# NTC.net
KiCad netlist of a schematic drawn in Altium Designer
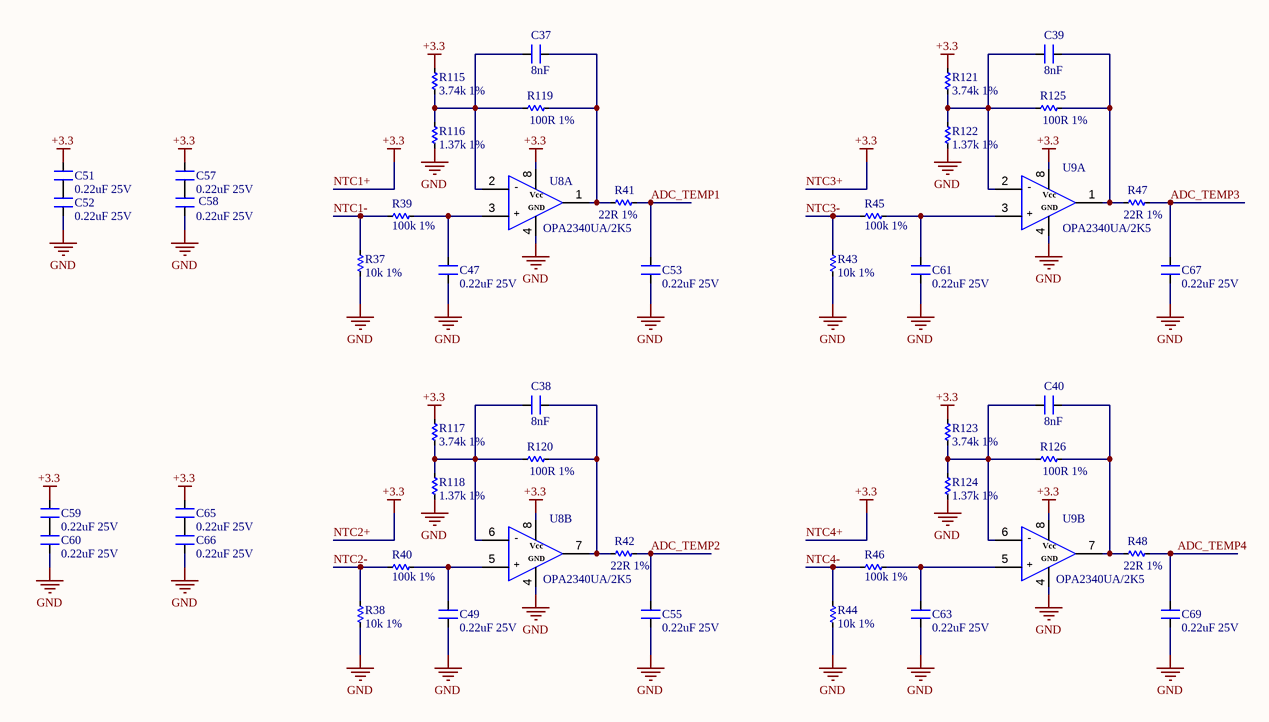
[diagram p0: NTC.SchDoc]

(export (version "E")
  (design (tool "Eeschema 10.0.6"))
  (components
    (comp (ref "C37")
      (value "8nF")
      (footprint "CN-SMD-0603")
      (libsource (lib "Sang_library") (part "Capacitors"))
    )
    (comp (ref "C38")
      (value "8nF")
      (footprint "CN-SMD-0603")
      (libsource (lib "Sang_library") (part "Capacitors"))
    )
    (comp (ref "C39")
      (value "8nF")
      (footprint "CN-SMD-0603")
      (libsource (lib "Sang_library") (part "Capacitors"))
    )
    (comp (ref "C40")
      (value "8nF")
      (footprint "CN-SMD-0603")
      (libsource (lib "Sang_library") (part "Capacitors"))
    )
    (comp (ref "C47")
      (value "0.22uF 25V")
      (footprint "CN-SMD-0603")
      (libsource (lib "Sang_library") (part "Capacitors"))
    )
    (comp (ref "C49")
      (value "0.22uF 25V")
      (footprint "CN-SMD-0603")
      (libsource (lib "Sang_library") (part "Capacitors"))
    )
    (comp (ref "C51")
      (value "0.22uF 25V")
      (footprint "CN-SMD-0603")
      (libsource (lib "Sang_library") (part "Capacitors"))
    )
    (comp (ref "C52")
      (value "0.22uF 25V")
      (footprint "CN-SMD-0603")
      (libsource (lib "Sang_library") (part "Capacitors"))
    )
    (comp (ref "C53")
      (value "0.22uF 25V")
      (footprint "CN-SMD-0603")
      (libsource (lib "Sang_library") (part "Capacitors"))
    )
    (comp (ref "C55")
      (value "0.22uF 25V")
      (footprint "CN-SMD-0603")
      (libsource (lib "Sang_library") (part "Capacitors"))
    )
    (comp (ref "C57")
      (value "0.22uF 25V")
      (footprint "CN-SMD-0603")
      (libsource (lib "Sang_library") (part "Capacitors"))
    )
    (comp (ref "C58")
      (value "0.22uF 25V")
      (footprint "CN-SMD-0603")
      (libsource (lib "Sang_library") (part "Capacitors"))
    )
    (comp (ref "C59")
      (value "0.22uF 25V")
      (footprint "CN-SMD-0603")
      (libsource (lib "Sang_library") (part "Capacitors"))
    )
    (comp (ref "C60")
      (value "0.22uF 25V")
      (footprint "CN-SMD-0603")
      (libsource (lib "Sang_library") (part "Capacitors"))
    )
    (comp (ref "C61")
      (value "0.22uF 25V")
      (footprint "CN-SMD-0603")
      (libsource (lib "Sang_library") (part "Capacitors"))
    )
    (comp (ref "C63")
      (value "0.22uF 25V")
      (footprint "CN-SMD-0603")
      (libsource (lib "Sang_library") (part "Capacitors"))
    )
    (comp (ref "C65")
      (value "0.22uF 25V")
      (footprint "CN-SMD-0603")
      (libsource (lib "Sang_library") (part "Capacitors"))
    )
    (comp (ref "C66")
      (value "0.22uF 25V")
      (footprint "CN-SMD-0603")
      (libsource (lib "Sang_library") (part "Capacitors"))
    )
    (comp (ref "C67")
      (value "0.22uF 25V")
      (footprint "CN-SMD-0603")
      (libsource (lib "Sang_library") (part "Capacitors"))
    )
    (comp (ref "C69")
      (value "0.22uF 25V")
      (footprint "CN-SMD-0603")
      (libsource (lib "Sang_library") (part "Capacitors"))
    )
    (comp (ref "R37")
      (value "10k 1%")
      (footprint "RES-SMD-0603")
      (description "SMD")
      (fields
        (field (name "MANUFACTURER") "Generic Components")
        (field (name "PUBLISHER") "Altium Hobart Technology Centre")
      )
      (libsource (lib "Sang_library") (part "Res SMD"))
    )
    (comp (ref "R38")
      (value "10k 1%")
      (footprint "RES-SMD-0603")
      (description "SMD")
      (fields
        (field (name "MANUFACTURER") "Generic Components")
        (field (name "PUBLISHER") "Altium Hobart Technology Centre")
      )
      (libsource (lib "Sang_library") (part "Res SMD"))
    )
    (comp (ref "R39")
      (value "100k 1%")
      (footprint "RES-SMD-0603")
      (description "SMD")
      (fields
        (field (name "MANUFACTURER") "Generic Components")
        (field (name "PUBLISHER") "Altium Hobart Technology Centre")
      )
      (libsource (lib "Sang_library") (part "Res SMD"))
    )
    (comp (ref "R40")
      (value "100k 1%")
      (footprint "RES-SMD-0603")
      (description "SMD")
      (fields
        (field (name "MANUFACTURER") "Generic Components")
        (field (name "PUBLISHER") "Altium Hobart Technology Centre")
      )
      (libsource (lib "Sang_library") (part "Res SMD"))
    )
    (comp (ref "R41")
      (value "22R 1%")
      (footprint "RES-SMD-0603")
      (description "SMD")
      (fields
        (field (name "MANUFACTURER") "Generic Components")
        (field (name "PUBLISHER") "Altium Hobart Technology Centre")
      )
      (libsource (lib "Sang_library") (part "Res SMD"))
    )
    (comp (ref "R42")
      (value "22R 1%")
      (footprint "RES-SMD-0603")
      (description "SMD")
      (fields
        (field (name "MANUFACTURER") "Generic Components")
        (field (name "PUBLISHER") "Altium Hobart Technology Centre")
      )
      (libsource (lib "Sang_library") (part "Res SMD"))
    )
    (comp (ref "R43")
      (value "10k 1%")
      (footprint "RES-SMD-0603")
      (description "SMD")
      (fields
        (field (name "MANUFACTURER") "Generic Components")
        (field (name "PUBLISHER") "Altium Hobart Technology Centre")
      )
      (libsource (lib "Sang_library") (part "Res SMD"))
    )
    (comp (ref "R44")
      (value "10k 1%")
      (footprint "RES-SMD-0603")
      (description "SMD")
      (fields
        (field (name "MANUFACTURER") "Generic Components")
        (field (name "PUBLISHER") "Altium Hobart Technology Centre")
      )
      (libsource (lib "Sang_library") (part "Res SMD"))
    )
    (comp (ref "R45")
      (value "100k 1%")
      (footprint "RES-SMD-0603")
      (description "SMD")
      (fields
        (field (name "MANUFACTURER") "Generic Components")
        (field (name "PUBLISHER") "Altium Hobart Technology Centre")
      )
      (libsource (lib "Sang_library") (part "Res SMD"))
    )
    (comp (ref "R46")
      (value "100k 1%")
      (footprint "RES-SMD-0603")
      (description "SMD")
      (fields
        (field (name "MANUFACTURER") "Generic Components")
        (field (name "PUBLISHER") "Altium Hobart Technology Centre")
      )
      (libsource (lib "Sang_library") (part "Res SMD"))
    )
    (comp (ref "R47")
      (value "22R 1%")
      (footprint "RES-SMD-0603")
      (description "SMD")
      (fields
        (field (name "MANUFACTURER") "Generic Components")
        (field (name "PUBLISHER") "Altium Hobart Technology Centre")
      )
      (libsource (lib "Sang_library") (part "Res SMD"))
    )
    (comp (ref "R48")
      (value "22R 1%")
      (footprint "RES-SMD-0603")
      (description "SMD")
      (fields
        (field (name "MANUFACTURER") "Generic Components")
        (field (name "PUBLISHER") "Altium Hobart Technology Centre")
      )
      (libsource (lib "Sang_library") (part "Res SMD"))
    )
    (comp (ref "R115")
      (value "3.74k 1%")
      (footprint "RES-SMD-0603")
      (description "SMD")
      (fields
        (field (name "MANUFACTURER") "Generic Components")
        (field (name "PUBLISHER") "Altium Hobart Technology Centre")
      )
      (libsource (lib "Sang_library") (part "Res SMD"))
    )
    (comp (ref "R116")
      (value "1.37k 1%")
      (footprint "RES-SMD-0603")
      (description "SMD")
      (fields
        (field (name "MANUFACTURER") "Generic Components")
        (field (name "PUBLISHER") "Altium Hobart Technology Centre")
      )
      (libsource (lib "Sang_library") (part "Res SMD"))
    )
    (comp (ref "R117")
      (value "3.74k 1%")
      (footprint "RES-SMD-0603")
      (description "SMD")
      (fields
        (field (name "MANUFACTURER") "Generic Components")
        (field (name "PUBLISHER") "Altium Hobart Technology Centre")
      )
      (libsource (lib "Sang_library") (part "Res SMD"))
    )
    (comp (ref "R118")
      (value "1.37k 1%")
      (footprint "RES-SMD-0603")
      (description "SMD")
      (fields
        (field (name "MANUFACTURER") "Generic Components")
        (field (name "PUBLISHER") "Altium Hobart Technology Centre")
      )
      (libsource (lib "Sang_library") (part "Res SMD"))
    )
    (comp (ref "R119")
      (value "100R 1%")
      (footprint "RES-SMD-0603")
      (description "SMD")
      (fields
        (field (name "MANUFACTURER") "Generic Components")
        (field (name "PUBLISHER") "Altium Hobart Technology Centre")
      )
      (libsource (lib "Sang_library") (part "Res SMD"))
    )
    (comp (ref "R120")
      (value "100R 1%")
      (footprint "RES-SMD-0603")
      (description "SMD")
      (fields
        (field (name "MANUFACTURER") "Generic Components")
        (field (name "PUBLISHER") "Altium Hobart Technology Centre")
      )
      (libsource (lib "Sang_library") (part "Res SMD"))
    )
    (comp (ref "R121")
      (value "3.74k 1%")
      (footprint "RES-SMD-0603")
      (description "SMD")
      (fields
        (field (name "MANUFACTURER") "Generic Components")
        (field (name "PUBLISHER") "Altium Hobart Technology Centre")
      )
      (libsource (lib "Sang_library") (part "Res SMD"))
    )
    (comp (ref "R122")
      (value "1.37k 1%")
      (footprint "RES-SMD-0603")
      (description "SMD")
      (fields
        (field (name "MANUFACTURER") "Generic Components")
        (field (name "PUBLISHER") "Altium Hobart Technology Centre")
      )
      (libsource (lib "Sang_library") (part "Res SMD"))
    )
    (comp (ref "R123")
      (value "3.74k 1%")
      (footprint "RES-SMD-0603")
      (description "SMD")
      (fields
        (field (name "MANUFACTURER") "Generic Components")
        (field (name "PUBLISHER") "Altium Hobart Technology Centre")
      )
      (libsource (lib "Sang_library") (part "Res SMD"))
    )
    (comp (ref "R124")
      (value "1.37k 1%")
      (footprint "RES-SMD-0603")
      (description "SMD")
      (fields
        (field (name "MANUFACTURER") "Generic Components")
        (field (name "PUBLISHER") "Altium Hobart Technology Centre")
      )
      (libsource (lib "Sang_library") (part "Res SMD"))
    )
    (comp (ref "R125")
      (value "100R 1%")
      (footprint "RES-SMD-0603")
      (description "SMD")
      (fields
        (field (name "MANUFACTURER") "Generic Components")
        (field (name "PUBLISHER") "Altium Hobart Technology Centre")
      )
      (libsource (lib "Sang_library") (part "Res SMD"))
    )
    (comp (ref "R126")
      (value "100R 1%")
      (footprint "RES-SMD-0603")
      (description "SMD")
      (fields
        (field (name "MANUFACTURER") "Generic Components")
        (field (name "PUBLISHER") "Altium Hobart Technology Centre")
      )
      (libsource (lib "Sang_library") (part "Res SMD"))
    )
    (comp (ref "U8")
      (value "OPA2340UA/2K5")
      (footprint "SO8")
      (libsource (lib "Sang_library") (part "OPA2340UA/2K5"))
    )
    (comp (ref "U9")
      (value "OPA2340UA/2K5")
      (footprint "SO8")
      (libsource (lib "Sang_library") (part "OPA2340UA/2K5"))
    )
  )
  (nets
    (net (code "1") (name "+3.3") (class "Default")
      (node (ref "C51") (pin "2") (pinfunction "2_2") (pintype "passive"))
      (node (ref "C57") (pin "2") (pinfunction "2_2") (pintype "passive"))
      (node (ref "C59") (pin "2") (pinfunction "2_2") (pintype "passive"))
      (node (ref "C65") (pin "2") (pinfunction "2_2") (pintype "passive"))
      (node (ref "R115") (pin "2") (pinfunction "2_2") (pintype "passive"))
      (node (ref "R117") (pin "2") (pinfunction "2_2") (pintype "passive"))
      (node (ref "R121") (pin "2") (pinfunction "2_2") (pintype "passive"))
      (node (ref "R123") (pin "2") (pinfunction "2_2") (pintype "passive"))
      (node (ref "U8") (pin "8") (pinfunction "8_8") (pintype "passive"))
      (node (ref "U9") (pin "8") (pinfunction "8_8") (pintype "passive"))
    )
    (net (code "2") (name "/ADC_TEMP1") (class "Default")
      (node (ref "C53") (pin "2") (pinfunction "2_2") (pintype "passive"))
      (node (ref "R41") (pin "2") (pinfunction "2_2") (pintype "passive"))
    )
    (net (code "3") (name "/ADC_TEMP2") (class "Default")
      (node (ref "C55") (pin "2") (pinfunction "2_2") (pintype "passive"))
      (node (ref "R42") (pin "2") (pinfunction "2_2") (pintype "passive"))
    )
    (net (code "4") (name "/ADC_TEMP3") (class "Default")
      (node (ref "C67") (pin "2") (pinfunction "2_2") (pintype "passive"))
      (node (ref "R47") (pin "2") (pinfunction "2_2") (pintype "passive"))
    )
    (net (code "5") (name "/ADC_TEMP4") (class "Default")
      (node (ref "C69") (pin "2") (pinfunction "2_2") (pintype "passive"))
      (node (ref "R48") (pin "2") (pinfunction "2_2") (pintype "passive"))
    )
    (net (code "6") (name "/NTC1-") (class "Default")
      (node (ref "R37") (pin "1") (pinfunction "1_1") (pintype "passive"))
      (node (ref "R39") (pin "1") (pinfunction "1_1") (pintype "passive"))
    )
    (net (code "7") (name "/NTC2-") (class "Default")
      (node (ref "R38") (pin "1") (pinfunction "1_1") (pintype "passive"))
      (node (ref "R40") (pin "1") (pinfunction "1_1") (pintype "passive"))
    )
    (net (code "8") (name "/NTC3-") (class "Default")
      (node (ref "R43") (pin "1") (pinfunction "1_1") (pintype "passive"))
      (node (ref "R45") (pin "1") (pinfunction "1_1") (pintype "passive"))
    )
    (net (code "9") (name "/NTC4-") (class "Default")
      (node (ref "R44") (pin "1") (pinfunction "1_1") (pintype "passive"))
      (node (ref "R46") (pin "1") (pinfunction "1_1") (pintype "passive"))
    )
    (net (code "10") (name "GND") (class "Default")
      (node (ref "C47") (pin "1") (pinfunction "1_1") (pintype "passive"))
      (node (ref "C49") (pin "1") (pinfunction "1_1") (pintype "passive"))
      (node (ref "C52") (pin "1") (pinfunction "1_1") (pintype "passive"))
      (node (ref "C53") (pin "1") (pinfunction "1_1") (pintype "passive"))
      (node (ref "C55") (pin "1") (pinfunction "1_1") (pintype "passive"))
      (node (ref "C58") (pin "1") (pinfunction "1_1") (pintype "passive"))
      (node (ref "C60") (pin "1") (pinfunction "1_1") (pintype "passive"))
      (node (ref "C61") (pin "1") (pinfunction "1_1") (pintype "passive"))
      (node (ref "C63") (pin "1") (pinfunction "1_1") (pintype "passive"))
      (node (ref "C66") (pin "1") (pinfunction "1_1") (pintype "passive"))
      (node (ref "C67") (pin "1") (pinfunction "1_1") (pintype "passive"))
      (node (ref "C69") (pin "1") (pinfunction "1_1") (pintype "passive"))
      (node (ref "R116") (pin "1") (pinfunction "1_1") (pintype "passive"))
      (node (ref "R118") (pin "1") (pinfunction "1_1") (pintype "passive"))
      (node (ref "R122") (pin "1") (pinfunction "1_1") (pintype "passive"))
      (node (ref "R124") (pin "1") (pinfunction "1_1") (pintype "passive"))
      (node (ref "R37") (pin "2") (pinfunction "2_2") (pintype "passive"))
      (node (ref "R38") (pin "2") (pinfunction "2_2") (pintype "passive"))
      (node (ref "R43") (pin "2") (pinfunction "2_2") (pintype "passive"))
      (node (ref "R44") (pin "2") (pinfunction "2_2") (pintype "passive"))
      (node (ref "U8") (pin "4") (pinfunction "4_4") (pintype "passive"))
      (node (ref "U9") (pin "4") (pinfunction "4_4") (pintype "passive"))
    )
    (net (code "11") (name "Net-(C37-Pad1)") (class "Default")
      (node (ref "C37") (pin "1") (pinfunction "1_1") (pintype "passive"))
      (node (ref "R119") (pin "2") (pinfunction "2_2") (pintype "passive"))
      (node (ref "R41") (pin "1") (pinfunction "1_1") (pintype "passive"))
      (node (ref "U8") (pin "1") (pinfunction "1_1") (pintype "passive"))
    )
    (net (code "12") (name "Net-(C37-Pad2)") (class "Default")
      (node (ref "C37") (pin "2") (pinfunction "2_2") (pintype "passive"))
      (node (ref "R115") (pin "1") (pinfunction "1_1") (pintype "passive"))
      (node (ref "R116") (pin "2") (pinfunction "2_2") (pintype "passive"))
      (node (ref "R119") (pin "1") (pinfunction "1_1") (pintype "passive"))
      (node (ref "U8") (pin "2") (pinfunction "2_2") (pintype "passive"))
    )
    (net (code "13") (name "Net-(C38-Pad1)") (class "Default")
      (node (ref "C38") (pin "1") (pinfunction "1_1") (pintype "passive"))
      (node (ref "R120") (pin "2") (pinfunction "2_2") (pintype "passive"))
      (node (ref "R42") (pin "1") (pinfunction "1_1") (pintype "passive"))
      (node (ref "U8") (pin "7") (pinfunction "7_7") (pintype "passive"))
    )
    (net (code "14") (name "Net-(C38-Pad2)") (class "Default")
      (node (ref "C38") (pin "2") (pinfunction "2_2") (pintype "passive"))
      (node (ref "R117") (pin "1") (pinfunction "1_1") (pintype "passive"))
      (node (ref "R118") (pin "2") (pinfunction "2_2") (pintype "passive"))
      (node (ref "R120") (pin "1") (pinfunction "1_1") (pintype "passive"))
      (node (ref "U8") (pin "6") (pinfunction "6_6") (pintype "passive"))
    )
    (net (code "15") (name "Net-(C39-Pad1)") (class "Default")
      (node (ref "C39") (pin "1") (pinfunction "1_1") (pintype "passive"))
      (node (ref "R125") (pin "2") (pinfunction "2_2") (pintype "passive"))
      (node (ref "R47") (pin "1") (pinfunction "1_1") (pintype "passive"))
      (node (ref "U9") (pin "1") (pinfunction "1_1") (pintype "passive"))
    )
    (net (code "16") (name "Net-(C39-Pad2)") (class "Default")
      (node (ref "C39") (pin "2") (pinfunction "2_2") (pintype "passive"))
      (node (ref "R121") (pin "1") (pinfunction "1_1") (pintype "passive"))
      (node (ref "R122") (pin "2") (pinfunction "2_2") (pintype "passive"))
      (node (ref "R125") (pin "1") (pinfunction "1_1") (pintype "passive"))
      (node (ref "U9") (pin "2") (pinfunction "2_2") (pintype "passive"))
    )
    (net (code "17") (name "Net-(C40-Pad1)") (class "Default")
      (node (ref "C40") (pin "1") (pinfunction "1_1") (pintype "passive"))
      (node (ref "R126") (pin "2") (pinfunction "2_2") (pintype "passive"))
      (node (ref "R48") (pin "1") (pinfunction "1_1") (pintype "passive"))
      (node (ref "U9") (pin "7") (pinfunction "7_7") (pintype "passive"))
    )
    (net (code "18") (name "Net-(C40-Pad2)") (class "Default")
      (node (ref "C40") (pin "2") (pinfunction "2_2") (pintype "passive"))
      (node (ref "R123") (pin "1") (pinfunction "1_1") (pintype "passive"))
      (node (ref "R124") (pin "2") (pinfunction "2_2") (pintype "passive"))
      (node (ref "R126") (pin "1") (pinfunction "1_1") (pintype "passive"))
      (node (ref "U9") (pin "6") (pinfunction "6_6") (pintype "passive"))
    )
    (net (code "19") (name "Net-(C47-Pad2)") (class "Default")
      (node (ref "C47") (pin "2") (pinfunction "2_2") (pintype "passive"))
      (node (ref "R39") (pin "2") (pinfunction "2_2") (pintype "passive"))
      (node (ref "U8") (pin "3") (pinfunction "3_3") (pintype "passive"))
    )
    (net (code "20") (name "Net-(C49-Pad2)") (class "Default")
      (node (ref "C49") (pin "2") (pinfunction "2_2") (pintype "passive"))
      (node (ref "R40") (pin "2") (pinfunction "2_2") (pintype "passive"))
      (node (ref "U8") (pin "5") (pinfunction "5_5") (pintype "passive"))
    )
    (net (code "21") (name "Net-(C51-Pad1)") (class "Default")
      (node (ref "C51") (pin "1") (pinfunction "1_1") (pintype "passive"))
      (node (ref "C52") (pin "2") (pinfunction "2_2") (pintype "passive"))
    )
    (net (code "22") (name "Net-(C57-Pad1)") (class "Default")
      (node (ref "C57") (pin "1") (pinfunction "1_1") (pintype "passive"))
      (node (ref "C58") (pin "2") (pinfunction "2_2") (pintype "passive"))
    )
    (net (code "23") (name "Net-(C59-Pad1)") (class "Default")
      (node (ref "C59") (pin "1") (pinfunction "1_1") (pintype "passive"))
      (node (ref "C60") (pin "2") (pinfunction "2_2") (pintype "passive"))
    )
    (net (code "24") (name "Net-(C61-Pad2)") (class "Default")
      (node (ref "C61") (pin "2") (pinfunction "2_2") (pintype "passive"))
      (node (ref "R45") (pin "2") (pinfunction "2_2") (pintype "passive"))
      (node (ref "U9") (pin "3") (pinfunction "3_3") (pintype "passive"))
    )
    (net (code "25") (name "Net-(C63-Pad2)") (class "Default")
      (node (ref "C63") (pin "2") (pinfunction "2_2") (pintype "passive"))
      (node (ref "R46") (pin "2") (pinfunction "2_2") (pintype "passive"))
      (node (ref "U9") (pin "5") (pinfunction "5_5") (pintype "passive"))
    )
    (net (code "26") (name "Net-(C65-Pad1)") (class "Default")
      (node (ref "C65") (pin "1") (pinfunction "1_1") (pintype "passive"))
      (node (ref "C66") (pin "2") (pinfunction "2_2") (pintype "passive"))
    )
  )
)
